# design.net
KiCad netlist of a schematic drawn in Altium Designer
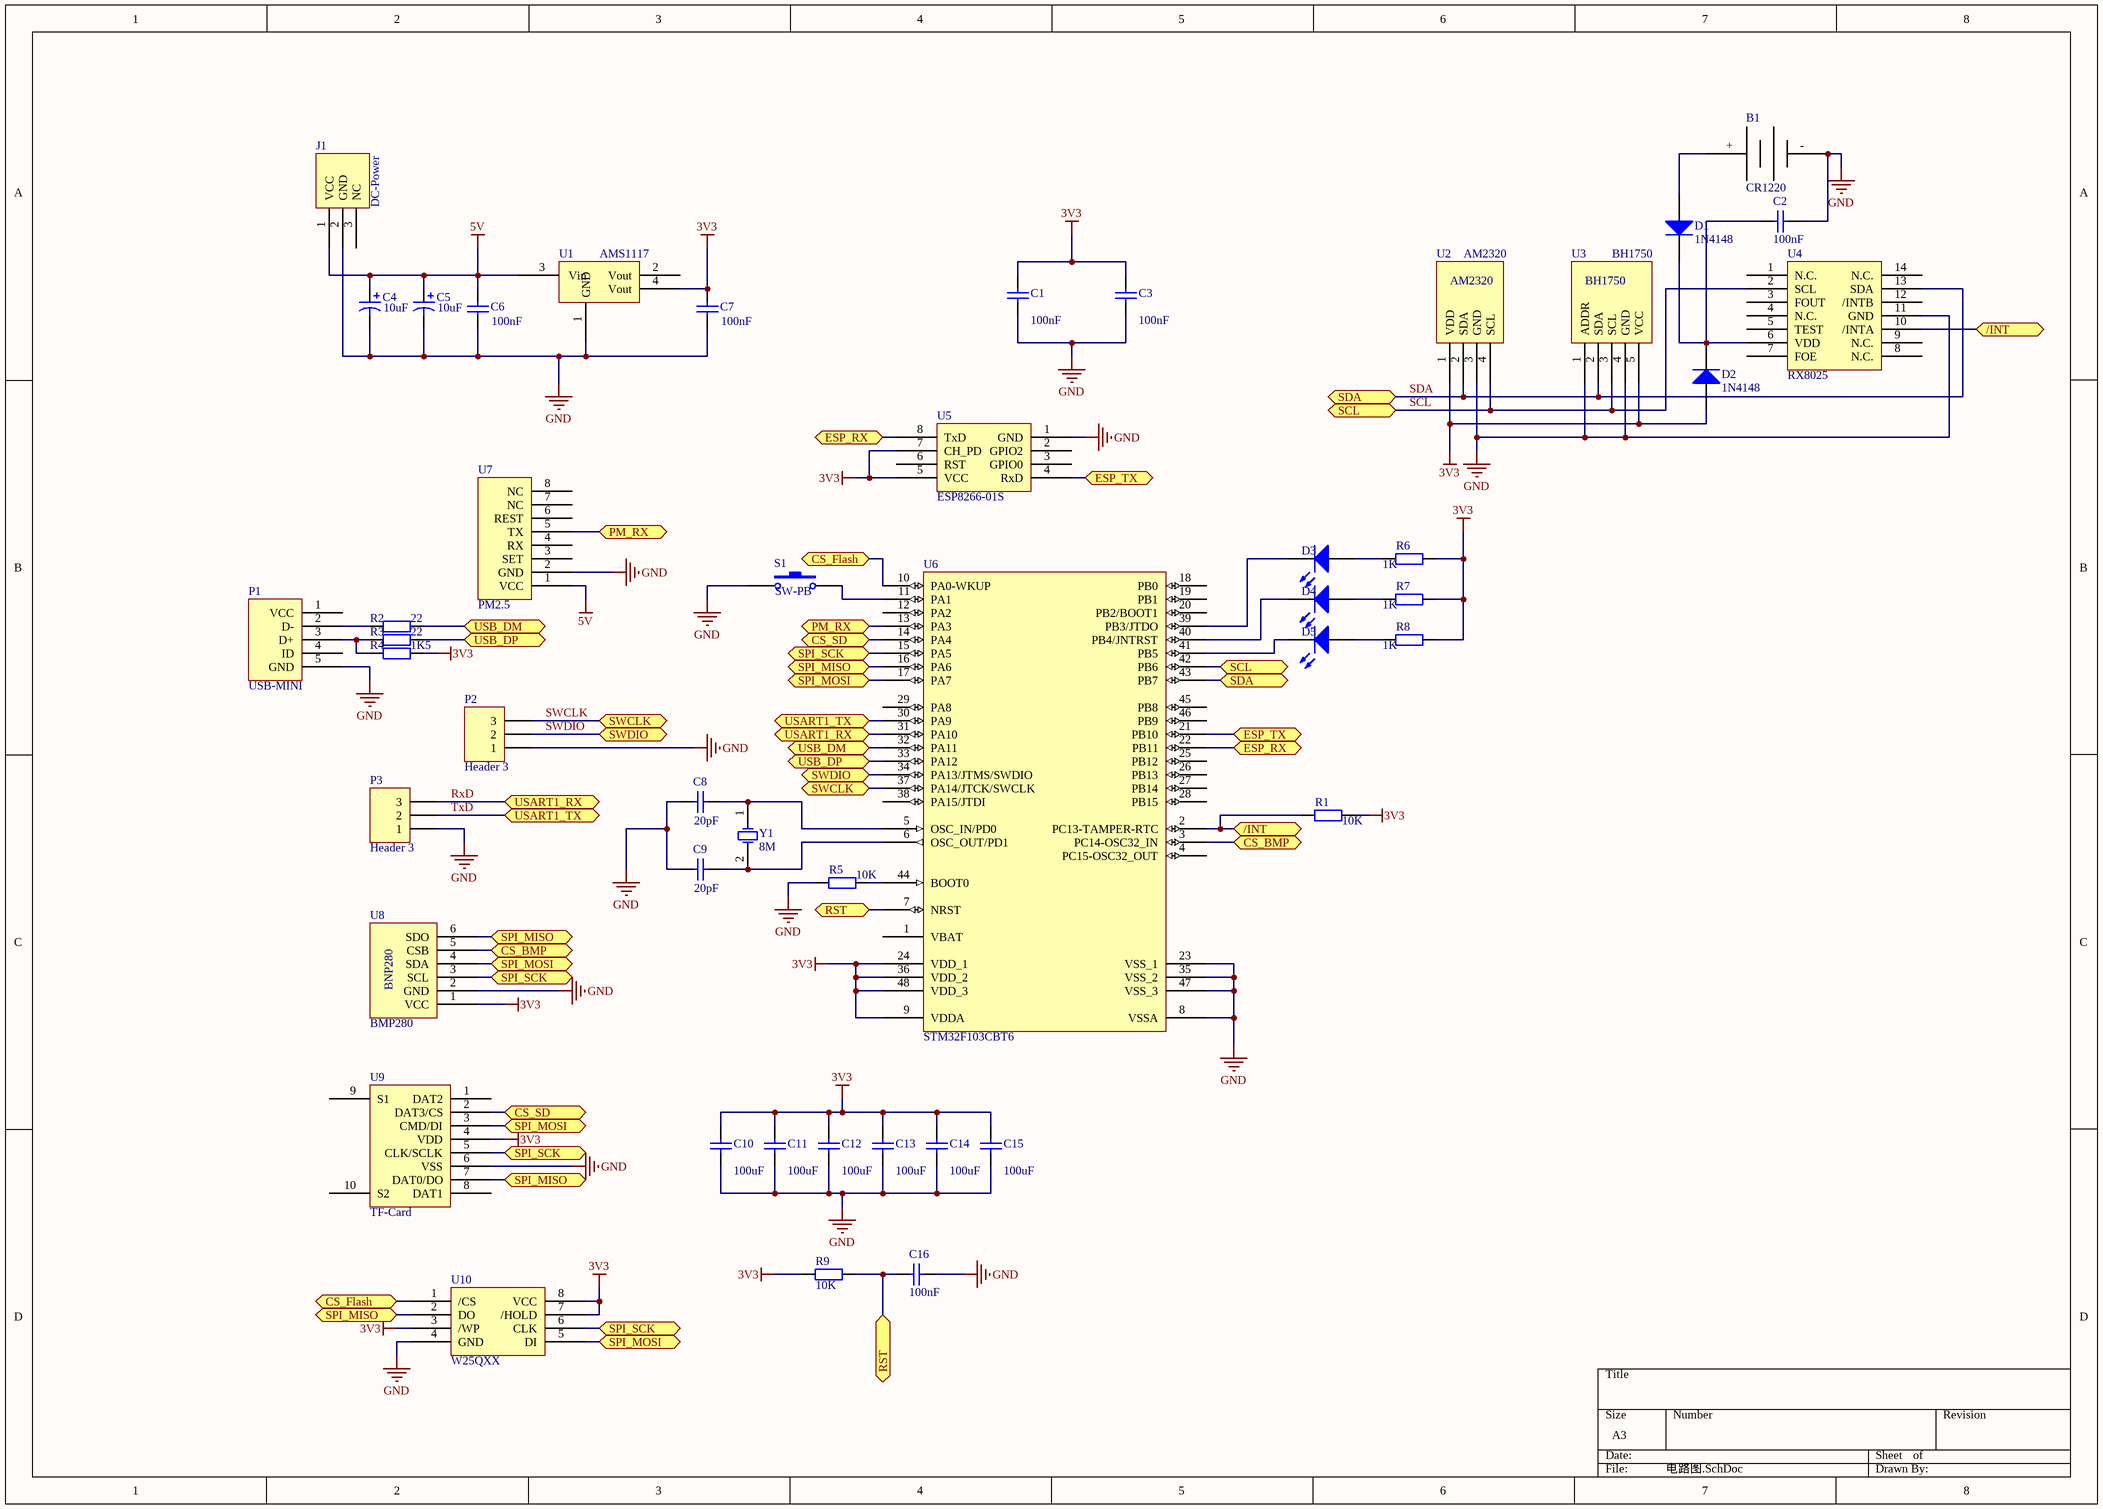
[diagram p0: 电路图.SchDoc]

(export (version "E")
  (design (tool "Eeschema 10.0.6"))
  (components
    (comp (ref "B1")
      (value "CR1220")
      (footprint "CR1220")
      (description "CR1220电池")
      (libsource (lib "元件") (part "CR1220"))
    )
    (comp (ref "C1")
      (value "100nF")
      (footprint "1608[0603]")
      (description "Capacitor")
      (fields (field (name "Comment") "Cap") (field (name "PUBLISHER") "Altium Limited"))
      (libsource (lib "Miscellaneous Devices") (part "Cap"))
    )
    (comp (ref "C2")
      (value "100nF")
      (footprint "1608[0603]")
      (description "Capacitor")
      (fields (field (name "Comment") "Cap") (field (name "PUBLISHER") "Altium Limited"))
      (libsource (lib "Miscellaneous Devices") (part "Cap"))
    )
    (comp (ref "C3")
      (value "100nF")
      (footprint "1608[0603]")
      (description "Capacitor")
      (fields (field (name "Comment") "Cap") (field (name "PUBLISHER") "Altium Limited"))
      (libsource (lib "Miscellaneous Devices") (part "Cap"))
    )
    (comp (ref "C4")
      (value "10uF")
      (footprint "C1210")
      (description "Polarized Capacitor (Radial)")
      (fields (field (name "Comment") "Cap Pol1") (field (name "PUBLISHER") "Altium Limited"))
      (libsource (lib "Miscellaneous Devices") (part "Cap Pol1"))
    )
    (comp (ref "C5")
      (value "10uF")
      (footprint "C1210")
      (description "Polarized Capacitor (Radial)")
      (fields (field (name "Comment") "Cap Pol1") (field (name "PUBLISHER") "Altium Limited"))
      (libsource (lib "Miscellaneous Devices") (part "Cap Pol1"))
    )
    (comp (ref "C6")
      (value "100nF")
      (footprint "1608[0603]")
      (description "Capacitor")
      (fields (field (name "Comment") "Cap") (field (name "PUBLISHER") "Altium Limited"))
      (libsource (lib "Miscellaneous Devices") (part "Cap"))
    )
    (comp (ref "C7")
      (value "100nF")
      (footprint "1608[0603]")
      (description "Capacitor")
      (fields (field (name "Comment") "Cap") (field (name "PUBLISHER") "Altium Limited"))
      (libsource (lib "Miscellaneous Devices") (part "Cap"))
    )
    (comp (ref "C8")
      (value "20pF")
      (footprint "C0805")
      (description "Capacitor")
      (fields (field (name "Comment") "Cap") (field (name "PUBLISHER") "Altium Limited"))
      (libsource (lib "Miscellaneous Devices") (part "Cap"))
    )
    (comp (ref "C9")
      (value "20pF")
      (footprint "C0805")
      (description "Capacitor")
      (fields (field (name "Comment") "Cap") (field (name "PUBLISHER") "Altium Limited"))
      (libsource (lib "Miscellaneous Devices") (part "Cap"))
    )
    (comp (ref "C10")
      (value "100uF")
      (footprint "1608[0603]")
      (description "Capacitor")
      (fields (field (name "Comment") "Cap") (field (name "PUBLISHER") "Altium Limited"))
      (libsource (lib "Miscellaneous Devices") (part "Cap"))
    )
    (comp (ref "C11")
      (value "100uF")
      (footprint "1608[0603]")
      (description "Capacitor")
      (fields (field (name "Comment") "Cap") (field (name "PUBLISHER") "Altium Limited"))
      (libsource (lib "Miscellaneous Devices") (part "Cap"))
    )
    (comp (ref "C12")
      (value "100uF")
      (footprint "1608[0603]")
      (description "Capacitor")
      (fields (field (name "Comment") "Cap") (field (name "PUBLISHER") "Altium Limited"))
      (libsource (lib "Miscellaneous Devices") (part "Cap"))
    )
    (comp (ref "C13")
      (value "100uF")
      (footprint "1608[0603]")
      (description "Capacitor")
      (fields (field (name "Comment") "Cap") (field (name "PUBLISHER") "Altium Limited"))
      (libsource (lib "Miscellaneous Devices") (part "Cap"))
    )
    (comp (ref "C14")
      (value "100uF")
      (footprint "1608[0603]")
      (description "Capacitor")
      (fields (field (name "Comment") "Cap") (field (name "PUBLISHER") "Altium Limited"))
      (libsource (lib "Miscellaneous Devices") (part "Cap"))
    )
    (comp (ref "C15")
      (value "100uF")
      (footprint "1608[0603]")
      (description "Capacitor")
      (fields (field (name "Comment") "Cap") (field (name "PUBLISHER") "Altium Limited"))
      (libsource (lib "Miscellaneous Devices") (part "Cap"))
    )
    (comp (ref "C16")
      (value "100nF")
      (footprint "1608[0603]")
      (description "Capacitor")
      (fields (field (name "Comment") "Cap") (field (name "PUBLISHER") "Altium Limited"))
      (libsource (lib "Miscellaneous Devices") (part "Cap"))
    )
    (comp (ref "D1")
      (value "1N4148")
      (footprint "DO-35")
      (description "High Conductance Fast Diode")
      (fields (field (name "PUBLISHER") "Altium Limited"))
      (libsource (lib "Miscellaneous Devices") (part "Diode 1N4148"))
    )
    (comp (ref "D2")
      (value "1N4148")
      (footprint "DO-35")
      (description "High Conductance Fast Diode")
      (fields (field (name "PUBLISHER") "Altium Limited"))
      (libsource (lib "Miscellaneous Devices") (part "Diode 1N4148"))
    )
    (comp (ref "D3")
      (value "LED2")
      (footprint "C0805")
      (description "Typical RED, GREEN, YELLOW, AMBER GaAs LED")
      (fields (field (name "PUBLISHER") "Altium Limited"))
      (libsource (lib "Miscellaneous Devices") (part "LED2"))
    )
    (comp (ref "D4")
      (value "LED2")
      (footprint "C0805")
      (description "Typical RED, GREEN, YELLOW, AMBER GaAs LED")
      (fields (field (name "PUBLISHER") "Altium Limited"))
      (libsource (lib "Miscellaneous Devices") (part "LED2"))
    )
    (comp (ref "D5")
      (value "LED2")
      (footprint "C0805")
      (description "Typical RED, GREEN, YELLOW, AMBER GaAs LED")
      (fields (field (name "PUBLISHER") "Altium Limited"))
      (libsource (lib "Miscellaneous Devices") (part "LED2"))
    )
    (comp (ref "J1") (value "DC-Power") (footprint "DC-Power") (libsource (lib "元件") (part "DC-Power")))
    (comp (ref "P1")
      (value "USB-MINI")
      (footprint "USB-MINI")
      (description "USB接口")
      (libsource (lib "元件") (part "USB-MINI"))
    )
    (comp (ref "P2")
      (value "Header 3")
      (footprint "HDR1X3")
      (description "Header, 3-Pin")
      (fields (field (name "PUBLISHER") "Altium Limited"))
      (libsource (lib "Miscellaneous Connectors") (part "Header 3"))
    )
    (comp (ref "P3")
      (value "Header 3")
      (footprint "HDR1X3")
      (description "Header, 3-Pin")
      (fields (field (name "PUBLISHER") "Altium Limited"))
      (libsource (lib "Miscellaneous Connectors") (part "Header 3"))
    )
    (comp (ref "R1")
      (value "10K")
      (footprint "1608[0603]")
      (description "Resistor")
      (fields (field (name "Comment") "Res2") (field (name "PUBLISHER") "Altium Limited"))
      (libsource (lib "Miscellaneous Devices") (part "Res2"))
    )
    (comp (ref "R2")
      (value "22")
      (footprint "C0805")
      (description "Resistor")
      (fields (field (name "Comment") "Res2") (field (name "PUBLISHER") "Altium Limited"))
      (libsource (lib "Miscellaneous Devices") (part "Res2"))
    )
    (comp (ref "R3")
      (value "22")
      (footprint "C0805")
      (description "Resistor")
      (fields (field (name "Comment") "Res2") (field (name "PUBLISHER") "Altium Limited"))
      (libsource (lib "Miscellaneous Devices") (part "Res2"))
    )
    (comp (ref "R4")
      (value "1K5")
      (footprint "C0805")
      (description "Resistor")
      (fields (field (name "Comment") "Res2") (field (name "PUBLISHER") "Altium Limited"))
      (libsource (lib "") (part "Res2_1"))
    )
    (comp (ref "R5")
      (value "10K")
      (footprint "1608[0603]")
      (description "Resistor")
      (fields (field (name "Comment") "Res2") (field (name "PUBLISHER") "Altium Limited"))
      (libsource (lib "Miscellaneous Devices") (part "Res2"))
    )
    (comp (ref "R6")
      (value "1K")
      (footprint "1608[0603]")
      (description "Resistor")
      (fields (field (name "Comment") "Res2") (field (name "PUBLISHER") "Altium Limited"))
      (libsource (lib "Miscellaneous Devices") (part "Res2"))
    )
    (comp (ref "R7")
      (value "1K")
      (footprint "1608[0603]")
      (description "Resistor")
      (fields (field (name "Comment") "Res2") (field (name "PUBLISHER") "Altium Limited"))
      (libsource (lib "Miscellaneous Devices") (part "Res2"))
    )
    (comp (ref "R8")
      (value "1K")
      (footprint "1608[0603]")
      (description "Resistor")
      (fields (field (name "Comment") "Res2") (field (name "PUBLISHER") "Altium Limited"))
      (libsource (lib "Miscellaneous Devices") (part "Res2"))
    )
    (comp (ref "R9")
      (value "10K")
      (footprint "1608[0603]")
      (description "Resistor")
      (fields (field (name "Comment") "Res2") (field (name "PUBLISHER") "Altium Limited"))
      (libsource (lib "") (part "Res2_1"))
    )
    (comp (ref "S1")
      (value "SW-PB")
      (footprint "KEY")
      (description "Switch")
      (fields (field (name "PUBLISHER") "Altium Limited"))
      (libsource (lib "Miscellaneous Devices") (part "SW-PB"))
    )
    (comp (ref "U1")
      (value "AMS1117")
      (footprint "SOT223_N")
      (description "稳压IC")
      (libsource (lib "元件") (part "AMS1117"))
    )
    (comp (ref "U2")
      (value "AM2320")
      (footprint "HDR1X4")
      (description "AM2320温湿度传感器")
      (libsource (lib "元件") (part "AM2320"))
    )
    (comp (ref "U3")
      (value "BH1750")
      (footprint "HDR1X5")
      (description "光照强度传感器")
      (libsource (lib "元件") (part "BH1750"))
    )
    (comp (ref "U4")
      (value "RX8025")
      (footprint "SOP14")
      (description "RTC芯片")
      (libsource (lib "元件") (part "RX8025"))
    )
    (comp (ref "U5")
      (value "ESP8266-01S")
      (footprint "ESP-8P")
      (description "WIFI模块")
      (libsource (lib "元件") (part "ESP8266-01S"))
    )
    (comp (ref "U6")
      (value "STM32F103CBT6")
      (footprint "LQFP48_L")
      (description "STM32 ARM-based 32-bit MCU with 128 Kbytes Flash, 48-pin LQFP, Industrial Temperature")
      (fields (field (name "PUBLISHER") "Altium Limited"))
      (libsource (lib "ST Microcontroller 32-Bit STM32") (part "STM32F103CBT6"))
    )
    (comp (ref "U7")
      (value "PM2.5")
      (footprint "PT-8P")
      (description "PM2.5传感器")
      (libsource (lib "元件") (part "PM2.5"))
    )
    (comp (ref "U8")
      (value "BMP280")
      (footprint "HDR1X6")
      (description "大气压传感器")
      (libsource (lib "元件") (part "BMP280"))
    )
    (comp (ref "U9")
      (value "TF-Card")
      (footprint "TF-Card")
      (description "TF存储卡")
      (libsource (lib "元件") (part "TF-Card"))
    )
    (comp (ref "U10")
      (value "W25QXX")
      (footprint "SOIC8")
      (description "SPI-Flash")
      (libsource (lib "元件") (part "W25QXX"))
    )
    (comp (ref "Y1")
      (value "8M")
      (footprint "OSC")
      (description "Crystal Oscillator")
      (fields (field (name "PUBLISHER") "Altium Limited"))
      (libsource (lib "Miscellaneous Devices") (part "XTAL"))
    )
  )
  (nets
    (net (code "1") (name "/CS_BMP") (class "Default")
      (node (ref "U6") (pin "3") (pinfunction "PC14-OSC32_IN_3") (pintype "bidirectional"))
      (node (ref "U8") (pin "5") (pinfunction "CSB_5") (pintype "passive"))
    )
    (net (code "2") (name "/CS_Flash") (class "Default")
      (node (ref "U10") (pin "1") (pinfunction "/CS_1") (pintype "passive"))
      (node (ref "U6") (pin "10") (pinfunction "PA0-WKUP_10") (pintype "bidirectional"))
    )
    (net (code "3") (name "/CS_SD") (class "Default")
      (node (ref "U6") (pin "14") (pinfunction "PA4_14") (pintype "bidirectional"))
      (node (ref "U9") (pin "2") (pinfunction "DAT3/CS_2") (pintype "passive"))
    )
    (net (code "4") (name "/ESP_RX") (class "Default")
      (node (ref "U5") (pin "8") (pinfunction "TxD_8") (pintype "passive"))
      (node (ref "U6") (pin "22") (pinfunction "PB11_22") (pintype "bidirectional"))
    )
    (net (code "5") (name "/ESP_TX") (class "Default")
      (node (ref "U5") (pin "4") (pinfunction "RxD_4") (pintype "passive"))
      (node (ref "U6") (pin "21") (pinfunction "PB10_21") (pintype "bidirectional"))
    )
    (net (code "6") (name "/PM_RX") (class "Default")
      (node (ref "U6") (pin "13") (pinfunction "PA3_13") (pintype "bidirectional"))
      (node (ref "U7") (pin "5") (pinfunction "TX_5") (pintype "passive"))
    )
    (net (code "7") (name "/RST") (class "Default")
      (node (ref "C16") (pin "2") (pinfunction "2_2") (pintype "passive"))
      (node (ref "R9") (pin "1") (pinfunction "1_1") (pintype "passive"))
      (node (ref "U6") (pin "7") (pinfunction "NRST_7") (pintype "bidirectional"))
    )
    (net (code "8") (name "/RxD") (class "Default")
      (node (ref "P3") (pin "3") (pinfunction "3_3") (pintype "passive"))
      (node (ref "U6") (pin "31") (pinfunction "PA10_31") (pintype "bidirectional"))
    )
    (net (code "9") (name "/SCL") (class "Default")
      (node (ref "U2") (pin "4") (pinfunction "SCL_4") (pintype "passive"))
      (node (ref "U3") (pin "3") (pinfunction "SCL_3") (pintype "passive"))
      (node (ref "U4") (pin "2") (pinfunction "SCL_2") (pintype "passive"))
      (node (ref "U6") (pin "42") (pinfunction "PB6_42") (pintype "bidirectional"))
    )
    (net (code "10") (name "/SDA") (class "Default")
      (node (ref "U2") (pin "2") (pinfunction "SDA_2") (pintype "passive"))
      (node (ref "U3") (pin "2") (pinfunction "SDA_2") (pintype "passive"))
      (node (ref "U4") (pin "13") (pinfunction "SDA_13") (pintype "passive"))
      (node (ref "U6") (pin "43") (pinfunction "PB7_43") (pintype "bidirectional"))
    )
    (net (code "11") (name "/SPI_MISO") (class "Default")
      (node (ref "U10") (pin "2") (pinfunction "DO_2") (pintype "passive"))
      (node (ref "U6") (pin "16") (pinfunction "PA6_16") (pintype "bidirectional"))
      (node (ref "U8") (pin "6") (pinfunction "SDO_6") (pintype "passive"))
      (node (ref "U9") (pin "7") (pinfunction "DAT0/DO_7") (pintype "passive"))
    )
    (net (code "12") (name "/SPI_MOSI") (class "Default")
      (node (ref "U10") (pin "5") (pinfunction "DI_5") (pintype "passive"))
      (node (ref "U6") (pin "17") (pinfunction "PA7_17") (pintype "bidirectional"))
      (node (ref "U8") (pin "4") (pinfunction "SDA_4") (pintype "passive"))
      (node (ref "U9") (pin "3") (pinfunction "CMD/DI_3") (pintype "passive"))
    )
    (net (code "13") (name "/SPI_SCK") (class "Default")
      (node (ref "U10") (pin "6") (pinfunction "CLK_6") (pintype "passive"))
      (node (ref "U6") (pin "15") (pinfunction "PA5_15") (pintype "bidirectional"))
      (node (ref "U8") (pin "3") (pinfunction "SCL_3") (pintype "passive"))
      (node (ref "U9") (pin "5") (pinfunction "CLK/SCLK_5") (pintype "passive"))
    )
    (net (code "14") (name "/SWCLK") (class "Default")
      (node (ref "P2") (pin "3") (pinfunction "3_3") (pintype "passive"))
      (node (ref "U6") (pin "37") (pinfunction "PA14/JTCK/SWCLK_37") (pintype "bidirectional"))
    )
    (net (code "15") (name "/SWDIO") (class "Default")
      (node (ref "P2") (pin "2") (pinfunction "2_2") (pintype "passive"))
      (node (ref "U6") (pin "34") (pinfunction "PA13/JTMS/SWDIO_34") (pintype "bidirectional"))
    )
    (net (code "16") (name "/TxD") (class "Default")
      (node (ref "P3") (pin "2") (pinfunction "2_2") (pintype "passive"))
      (node (ref "U6") (pin "30") (pinfunction "PA9_30") (pintype "bidirectional"))
    )
    (net (code "17") (name "/USB_DM") (class "Default")
      (node (ref "R2") (pin "2") (pinfunction "2_2") (pintype "passive"))
      (node (ref "U6") (pin "32") (pinfunction "PA11_32") (pintype "bidirectional"))
    )
    (net (code "18") (name "/USB_DP") (class "Default")
      (node (ref "R3") (pin "2") (pinfunction "2_2") (pintype "passive"))
      (node (ref "U6") (pin "33") (pinfunction "PA12_33") (pintype "bidirectional"))
    )
    (net (code "19") (name "/{slash}INT") (class "Default")
      (node (ref "R1") (pin "1") (pinfunction "1_1") (pintype "passive"))
      (node (ref "U4") (pin "10") (pinfunction "/INTA_10") (pintype "passive"))
      (node (ref "U6") (pin "2") (pinfunction "PC13-TAMPER-RTC_2") (pintype "bidirectional"))
    )
    (net (code "20") (name "3V3") (class "Default")
      (node (ref "C1") (pin "2") (pinfunction "2_2") (pintype "passive"))
      (node (ref "C10") (pin "2") (pinfunction "2_2") (pintype "passive"))
      (node (ref "C11") (pin "2") (pinfunction "2_2") (pintype "passive"))
      (node (ref "C12") (pin "2") (pinfunction "2_2") (pintype "passive"))
      (node (ref "C13") (pin "2") (pinfunction "2_2") (pintype "passive"))
      (node (ref "C14") (pin "2") (pinfunction "2_2") (pintype "passive"))
      (node (ref "C15") (pin "2") (pinfunction "2_2") (pintype "passive"))
      (node (ref "C3") (pin "2") (pinfunction "2_2") (pintype "passive"))
      (node (ref "C7") (pin "2") (pinfunction "2_2") (pintype "passive"))
      (node (ref "D2") (pin "1") (pinfunction "A_1") (pintype "passive"))
      (node (ref "R1") (pin "2") (pinfunction "2_2") (pintype "passive"))
      (node (ref "R4") (pin "1") (pinfunction "1_1") (pintype "passive"))
      (node (ref "R6") (pin "2") (pinfunction "2_2") (pintype "passive"))
      (node (ref "R7") (pin "2") (pinfunction "2_2") (pintype "passive"))
      (node (ref "R8") (pin "2") (pinfunction "2_2") (pintype "passive"))
      (node (ref "R9") (pin "2") (pinfunction "2_2") (pintype "passive"))
      (node (ref "U1") (pin "4") (pinfunction "Vout_4") (pintype "passive"))
      (node (ref "U10") (pin "3") (pinfunction "/WP_3") (pintype "passive"))
      (node (ref "U10") (pin "7") (pinfunction "/HOLD_7") (pintype "passive"))
      (node (ref "U10") (pin "8") (pinfunction "VCC_8") (pintype "passive"))
      (node (ref "U2") (pin "1") (pinfunction "VDD_1") (pintype "passive"))
      (node (ref "U3") (pin "5") (pinfunction "VCC_5") (pintype "passive"))
      (node (ref "U5") (pin "5") (pinfunction "VCC_5") (pintype "passive"))
      (node (ref "U5") (pin "7") (pinfunction "CH_PD_7") (pintype "passive"))
      (node (ref "U6") (pin "24") (pinfunction "VDD_1_24") (pintype "power_in"))
      (node (ref "U6") (pin "36") (pinfunction "VDD_2_36") (pintype "power_in"))
      (node (ref "U6") (pin "48") (pinfunction "VDD_3_48") (pintype "power_in"))
      (node (ref "U6") (pin "9") (pinfunction "VDDA_9") (pintype "power_in"))
      (node (ref "U8") (pin "1") (pinfunction "VCC_1") (pintype "passive"))
      (node (ref "U9") (pin "4") (pinfunction "VDD_4") (pintype "passive"))
    )
    (net (code "21") (name "5V") (class "Default")
      (node (ref "C4") (pin "1") (pinfunction "1_1") (pintype "passive"))
      (node (ref "C5") (pin "1") (pinfunction "1_1") (pintype "passive"))
      (node (ref "C6") (pin "2") (pinfunction "2_2") (pintype "passive"))
      (node (ref "J1") (pin "1") (pinfunction "VCC_1") (pintype "passive"))
      (node (ref "U1") (pin "3") (pinfunction "Vin_3") (pintype "passive"))
      (node (ref "U7") (pin "1") (pinfunction "VCC_1") (pintype "passive"))
    )
    (net (code "22") (name "GND") (class "Default")
      (node (ref "B1") (pin "-") (pinfunction "0_-") (pintype "passive"))
      (node (ref "C1") (pin "1") (pinfunction "1_1") (pintype "passive"))
      (node (ref "C10") (pin "1") (pinfunction "1_1") (pintype "passive"))
      (node (ref "C11") (pin "1") (pinfunction "1_1") (pintype "passive"))
      (node (ref "C12") (pin "1") (pinfunction "1_1") (pintype "passive"))
      (node (ref "C13") (pin "1") (pinfunction "1_1") (pintype "passive"))
      (node (ref "C14") (pin "1") (pinfunction "1_1") (pintype "passive"))
      (node (ref "C15") (pin "1") (pinfunction "1_1") (pintype "passive"))
      (node (ref "C16") (pin "1") (pinfunction "1_1") (pintype "passive"))
      (node (ref "C2") (pin "1") (pinfunction "1_1") (pintype "passive"))
      (node (ref "C3") (pin "1") (pinfunction "1_1") (pintype "passive"))
      (node (ref "C4") (pin "2") (pinfunction "2_2") (pintype "passive"))
      (node (ref "C5") (pin "2") (pinfunction "2_2") (pintype "passive"))
      (node (ref "C6") (pin "1") (pinfunction "1_1") (pintype "passive"))
      (node (ref "C7") (pin "1") (pinfunction "1_1") (pintype "passive"))
      (node (ref "C8") (pin "1") (pinfunction "1_1") (pintype "passive"))
      (node (ref "C9") (pin "1") (pinfunction "1_1") (pintype "passive"))
      (node (ref "J1") (pin "2") (pinfunction "GND_2") (pintype "passive"))
      (node (ref "P1") (pin "5") (pinfunction "GND_5") (pintype "passive"))
      (node (ref "P2") (pin "1") (pinfunction "1_1") (pintype "passive"))
      (node (ref "P3") (pin "1") (pinfunction "1_1") (pintype "passive"))
      (node (ref "R5") (pin "1") (pinfunction "1_1") (pintype "passive"))
      (node (ref "S1") (pin "1") (pinfunction "1_1") (pintype "passive"))
      (node (ref "U1") (pin "1") (pinfunction "GND_1") (pintype "passive"))
      (node (ref "U10") (pin "4") (pinfunction "GND_4") (pintype "passive"))
      (node (ref "U2") (pin "3") (pinfunction "GND_3") (pintype "passive"))
      (node (ref "U3") (pin "1") (pinfunction "ADDR_1") (pintype "passive"))
      (node (ref "U3") (pin "4") (pinfunction "GND_4") (pintype "passive"))
      (node (ref "U4") (pin "11") (pinfunction "GND_11") (pintype "passive"))
      (node (ref "U5") (pin "1") (pinfunction "GND_1") (pintype "passive"))
      (node (ref "U6") (pin "23") (pinfunction "VSS_1_23") (pintype "power_in"))
      (node (ref "U6") (pin "35") (pinfunction "VSS_2_35") (pintype "power_in"))
      (node (ref "U6") (pin "47") (pinfunction "VSS_3_47") (pintype "power_in"))
      (node (ref "U6") (pin "8") (pinfunction "VSSA_8") (pintype "power_in"))
      (node (ref "U7") (pin "2") (pinfunction "GND_2") (pintype "passive"))
      (node (ref "U8") (pin "2") (pinfunction "GND_2") (pintype "passive"))
      (node (ref "U9") (pin "6") (pinfunction "VSS_6") (pintype "passive"))
    )
    (net (code "23") (name "Net-(B1-1)") (class "Default")
      (node (ref "B1") (pin "+") (pinfunction "1_+") (pintype "passive"))
      (node (ref "D1") (pin "1") (pinfunction "A_1") (pintype "passive"))
    )
    (net (code "24") (name "Net-(D1-K)") (class "Default")
      (node (ref "C2") (pin "2") (pinfunction "2_2") (pintype "passive"))
      (node (ref "D1") (pin "2") (pinfunction "K_2") (pintype "passive"))
      (node (ref "D2") (pin "2") (pinfunction "K_2") (pintype "passive"))
      (node (ref "U4") (pin "6") (pinfunction "VDD_6") (pintype "passive"))
    )
    (net (code "25") (name "Net-(D3-A)") (class "Default")
      (node (ref "D3") (pin "1") (pinfunction "A_1") (pintype "passive"))
      (node (ref "R6") (pin "1") (pinfunction "1_1") (pintype "passive"))
    )
    (net (code "26") (name "Net-(D3-K)") (class "Default")
      (node (ref "D3") (pin "2") (pinfunction "K_2") (pintype "passive"))
      (node (ref "U6") (pin "39") (pinfunction "PB3/JTDO_39") (pintype "bidirectional"))
    )
    (net (code "27") (name "Net-(D4-A)") (class "Default")
      (node (ref "D4") (pin "1") (pinfunction "A_1") (pintype "passive"))
      (node (ref "R7") (pin "1") (pinfunction "1_1") (pintype "passive"))
    )
    (net (code "28") (name "Net-(D4-K)") (class "Default")
      (node (ref "D4") (pin "2") (pinfunction "K_2") (pintype "passive"))
      (node (ref "U6") (pin "40") (pinfunction "PB4/JNTRST_40") (pintype "bidirectional"))
    )
    (net (code "29") (name "Net-(D5-A)") (class "Default")
      (node (ref "D5") (pin "1") (pinfunction "A_1") (pintype "passive"))
      (node (ref "R8") (pin "1") (pinfunction "1_1") (pintype "passive"))
    )
    (net (code "30") (name "Net-(D5-K)") (class "Default")
      (node (ref "D5") (pin "2") (pinfunction "K_2") (pintype "passive"))
      (node (ref "U6") (pin "41") (pinfunction "PB5_41") (pintype "bidirectional"))
    )
    (net (code "31") (name "Net-(P1-D+)") (class "Default")
      (node (ref "P1") (pin "3") (pinfunction "D+_3") (pintype "passive"))
      (node (ref "R3") (pin "1") (pinfunction "1_1") (pintype "passive"))
      (node (ref "R4") (pin "2") (pinfunction "2_2") (pintype "passive"))
    )
    (net (code "32") (name "Net-(P1-D-)") (class "Default")
      (node (ref "P1") (pin "2") (pinfunction "D-_2") (pintype "passive"))
      (node (ref "R2") (pin "1") (pinfunction "1_1") (pintype "passive"))
    )
    (net (code "33") (name "Net-(U6-BOOT0)") (class "Default")
      (node (ref "R5") (pin "2") (pinfunction "2_2") (pintype "passive"))
      (node (ref "U6") (pin "44") (pinfunction "BOOT0_44") (pintype "input"))
    )
    (net (code "34") (name "Net-(U6-OSC_IN{slash}PD0)") (class "Default")
      (node (ref "C8") (pin "2") (pinfunction "2_2") (pintype "passive"))
      (node (ref "U6") (pin "5") (pinfunction "OSC_IN/PD0_5") (pintype "input"))
      (node (ref "Y1") (pin "1") (pinfunction "OSC1_1") (pintype "passive"))
    )
    (net (code "35") (name "Net-(U6-OSC_OUT{slash}PD1)") (class "Default")
      (node (ref "C9") (pin "2") (pinfunction "2_2") (pintype "passive"))
      (node (ref "U6") (pin "6") (pinfunction "OSC_OUT/PD1_6") (pintype "output"))
      (node (ref "Y1") (pin "2") (pinfunction "OSC2_2") (pintype "passive"))
    )
    (net (code "36") (name "Net-(U6-PA1)") (class "Default")
      (node (ref "S1") (pin "2") (pinfunction "2_2") (pintype "passive"))
      (node (ref "U6") (pin "11") (pinfunction "PA1_11") (pintype "bidirectional"))
    )
    (net (code "37") (name "unconnected-(J1-NC-Pad3)") (class "Default")
      (node (ref "J1") (pin "3") (pinfunction "NC_3") (pintype "passive"))
    )
    (net (code "38") (name "unconnected-(P1-ID-Pad4)") (class "Default")
      (node (ref "P1") (pin "4") (pinfunction "ID_4") (pintype "passive"))
    )
    (net (code "39") (name "unconnected-(P1-VCC-Pad1)") (class "Default")
      (node (ref "P1") (pin "1") (pinfunction "VCC_1") (pintype "passive"))
    )
    (net (code "40") (name "unconnected-(U1-Vout-Pad2)") (class "Default")
      (node (ref "U1") (pin "2") (pinfunction "Vout_2") (pintype "power_in"))
    )
    (net (code "41") (name "unconnected-(U4-FOE-Pad7)") (class "Default")
      (node (ref "U4") (pin "7") (pinfunction "FOE_7") (pintype "passive"))
    )
    (net (code "42") (name "unconnected-(U4-FOUT-Pad3)") (class "Default")
      (node (ref "U4") (pin "3") (pinfunction "FOUT_3") (pintype "passive"))
    )
    (net (code "43") (name "unconnected-(U4-N.C.-Pad1)") (class "Default")
      (node (ref "U4") (pin "1") (pinfunction "N.C._1") (pintype "passive"))
    )
    (net (code "44") (name "unconnected-(U4-N.C.-Pad4)") (class "Default")
      (node (ref "U4") (pin "4") (pinfunction "N.C._4") (pintype "passive"))
    )
    (net (code "45") (name "unconnected-(U4-N.C.-Pad8)") (class "Default")
      (node (ref "U4") (pin "8") (pinfunction "N.C._8") (pintype "passive"))
    )
    (net (code "46") (name "unconnected-(U4-N.C.-Pad9)") (class "Default")
      (node (ref "U4") (pin "9") (pinfunction "N.C._9") (pintype "passive"))
    )
    (net (code "47") (name "unconnected-(U4-N.C.-Pad14)") (class "Default")
      (node (ref "U4") (pin "14") (pinfunction "N.C._14") (pintype "passive"))
    )
    (net (code "48") (name "unconnected-(U4-TEST-Pad5)") (class "Default")
      (node (ref "U4") (pin "5") (pinfunction "TEST_5") (pintype "passive"))
    )
    (net (code "49") (name "unconnected-(U4-{slash}INTB-Pad12)") (class "Default")
      (node (ref "U4") (pin "12") (pinfunction "/INTB_12") (pintype "passive"))
    )
    (net (code "50") (name "unconnected-(U5-GPIO0-Pad3)") (class "Default")
      (node (ref "U5") (pin "3") (pinfunction "GPIO0_3") (pintype "passive"))
    )
    (net (code "51") (name "unconnected-(U5-GPIO2-Pad2)") (class "Default")
      (node (ref "U5") (pin "2") (pinfunction "GPIO2_2") (pintype "passive"))
    )
    (net (code "52") (name "unconnected-(U5-RST-Pad6)") (class "Default")
      (node (ref "U5") (pin "6") (pinfunction "RST_6") (pintype "passive"))
    )
    (net (code "53") (name "unconnected-(U6-PA2-Pad12)") (class "Default")
      (node (ref "U6") (pin "12") (pinfunction "PA2_12") (pintype "bidirectional"))
    )
    (net (code "54") (name "unconnected-(U6-PA8-Pad29)") (class "Default")
      (node (ref "U6") (pin "29") (pinfunction "PA8_29") (pintype "bidirectional"))
    )
    (net (code "55") (name "unconnected-(U6-PA15{slash}JTDI-Pad38)") (class "Default")
      (node (ref "U6") (pin "38") (pinfunction "PA15/JTDI_38") (pintype "bidirectional"))
    )
    (net (code "56") (name "unconnected-(U6-PB0-Pad18)") (class "Default")
      (node (ref "U6") (pin "18") (pinfunction "PB0_18") (pintype "bidirectional"))
    )
    (net (code "57") (name "unconnected-(U6-PB1-Pad19)") (class "Default")
      (node (ref "U6") (pin "19") (pinfunction "PB1_19") (pintype "bidirectional"))
    )
    (net (code "58") (name "unconnected-(U6-PB2{slash}BOOT1-Pad20)") (class "Default")
      (node (ref "U6") (pin "20") (pinfunction "PB2/BOOT1_20") (pintype "bidirectional"))
    )
    (net (code "59") (name "unconnected-(U6-PB8-Pad45)") (class "Default")
      (node (ref "U6") (pin "45") (pinfunction "PB8_45") (pintype "bidirectional"))
    )
    (net (code "60") (name "unconnected-(U6-PB9-Pad46)") (class "Default")
      (node (ref "U6") (pin "46") (pinfunction "PB9_46") (pintype "bidirectional"))
    )
    (net (code "61") (name "unconnected-(U6-PB12-Pad25)") (class "Default")
      (node (ref "U6") (pin "25") (pinfunction "PB12_25") (pintype "bidirectional"))
    )
    (net (code "62") (name "unconnected-(U6-PB13-Pad26)") (class "Default")
      (node (ref "U6") (pin "26") (pinfunction "PB13_26") (pintype "bidirectional"))
    )
    (net (code "63") (name "unconnected-(U6-PB14-Pad27)") (class "Default")
      (node (ref "U6") (pin "27") (pinfunction "PB14_27") (pintype "bidirectional"))
    )
    (net (code "64") (name "unconnected-(U6-PB15-Pad28)") (class "Default")
      (node (ref "U6") (pin "28") (pinfunction "PB15_28") (pintype "bidirectional"))
    )
    (net (code "65") (name "unconnected-(U6-PC15-OSC32_OUT-Pad4)") (class "Default")
      (node (ref "U6") (pin "4") (pinfunction "PC15-OSC32_OUT_4") (pintype "bidirectional"))
    )
    (net (code "66") (name "unconnected-(U6-VBAT-Pad1)") (class "Default")
      (node (ref "U6") (pin "1") (pinfunction "VBAT_1") (pintype "power_in"))
    )
    (net (code "67") (name "unconnected-(U7-NC-Pad7)") (class "Default")
      (node (ref "U7") (pin "7") (pinfunction "NC_7") (pintype "passive"))
    )
    (net (code "68") (name "unconnected-(U7-NC-Pad8)") (class "Default")
      (node (ref "U7") (pin "8") (pinfunction "NC_8") (pintype "passive"))
    )
    (net (code "69") (name "unconnected-(U7-REST-Pad6)") (class "Default")
      (node (ref "U7") (pin "6") (pinfunction "REST_6") (pintype "passive"))
    )
    (net (code "70") (name "unconnected-(U7-RX-Pad4)") (class "Default")
      (node (ref "U7") (pin "4") (pinfunction "RX_4") (pintype "passive"))
    )
    (net (code "71") (name "unconnected-(U7-SET-Pad3)") (class "Default")
      (node (ref "U7") (pin "3") (pinfunction "SET_3") (pintype "passive"))
    )
    (net (code "72") (name "unconnected-(U9-DAT1-Pad8)") (class "Default")
      (node (ref "U9") (pin "8") (pinfunction "DAT1_8") (pintype "passive"))
    )
    (net (code "73") (name "unconnected-(U9-DAT2-Pad1)") (class "Default")
      (node (ref "U9") (pin "1") (pinfunction "DAT2_1") (pintype "passive"))
    )
    (net (code "74") (name "unconnected-(U9-S1-Pad9)") (class "Default")
      (node (ref "U9") (pin "9") (pinfunction "S1_9") (pintype "passive"))
    )
    (net (code "75") (name "unconnected-(U9-S2-Pad10)") (class "Default")
      (node (ref "U9") (pin "10") (pinfunction "S2_10") (pintype "passive"))
    )
  )
)
